# 01_DEBUG.net
KiCad netlist of a schematic drawn in Altium Designer
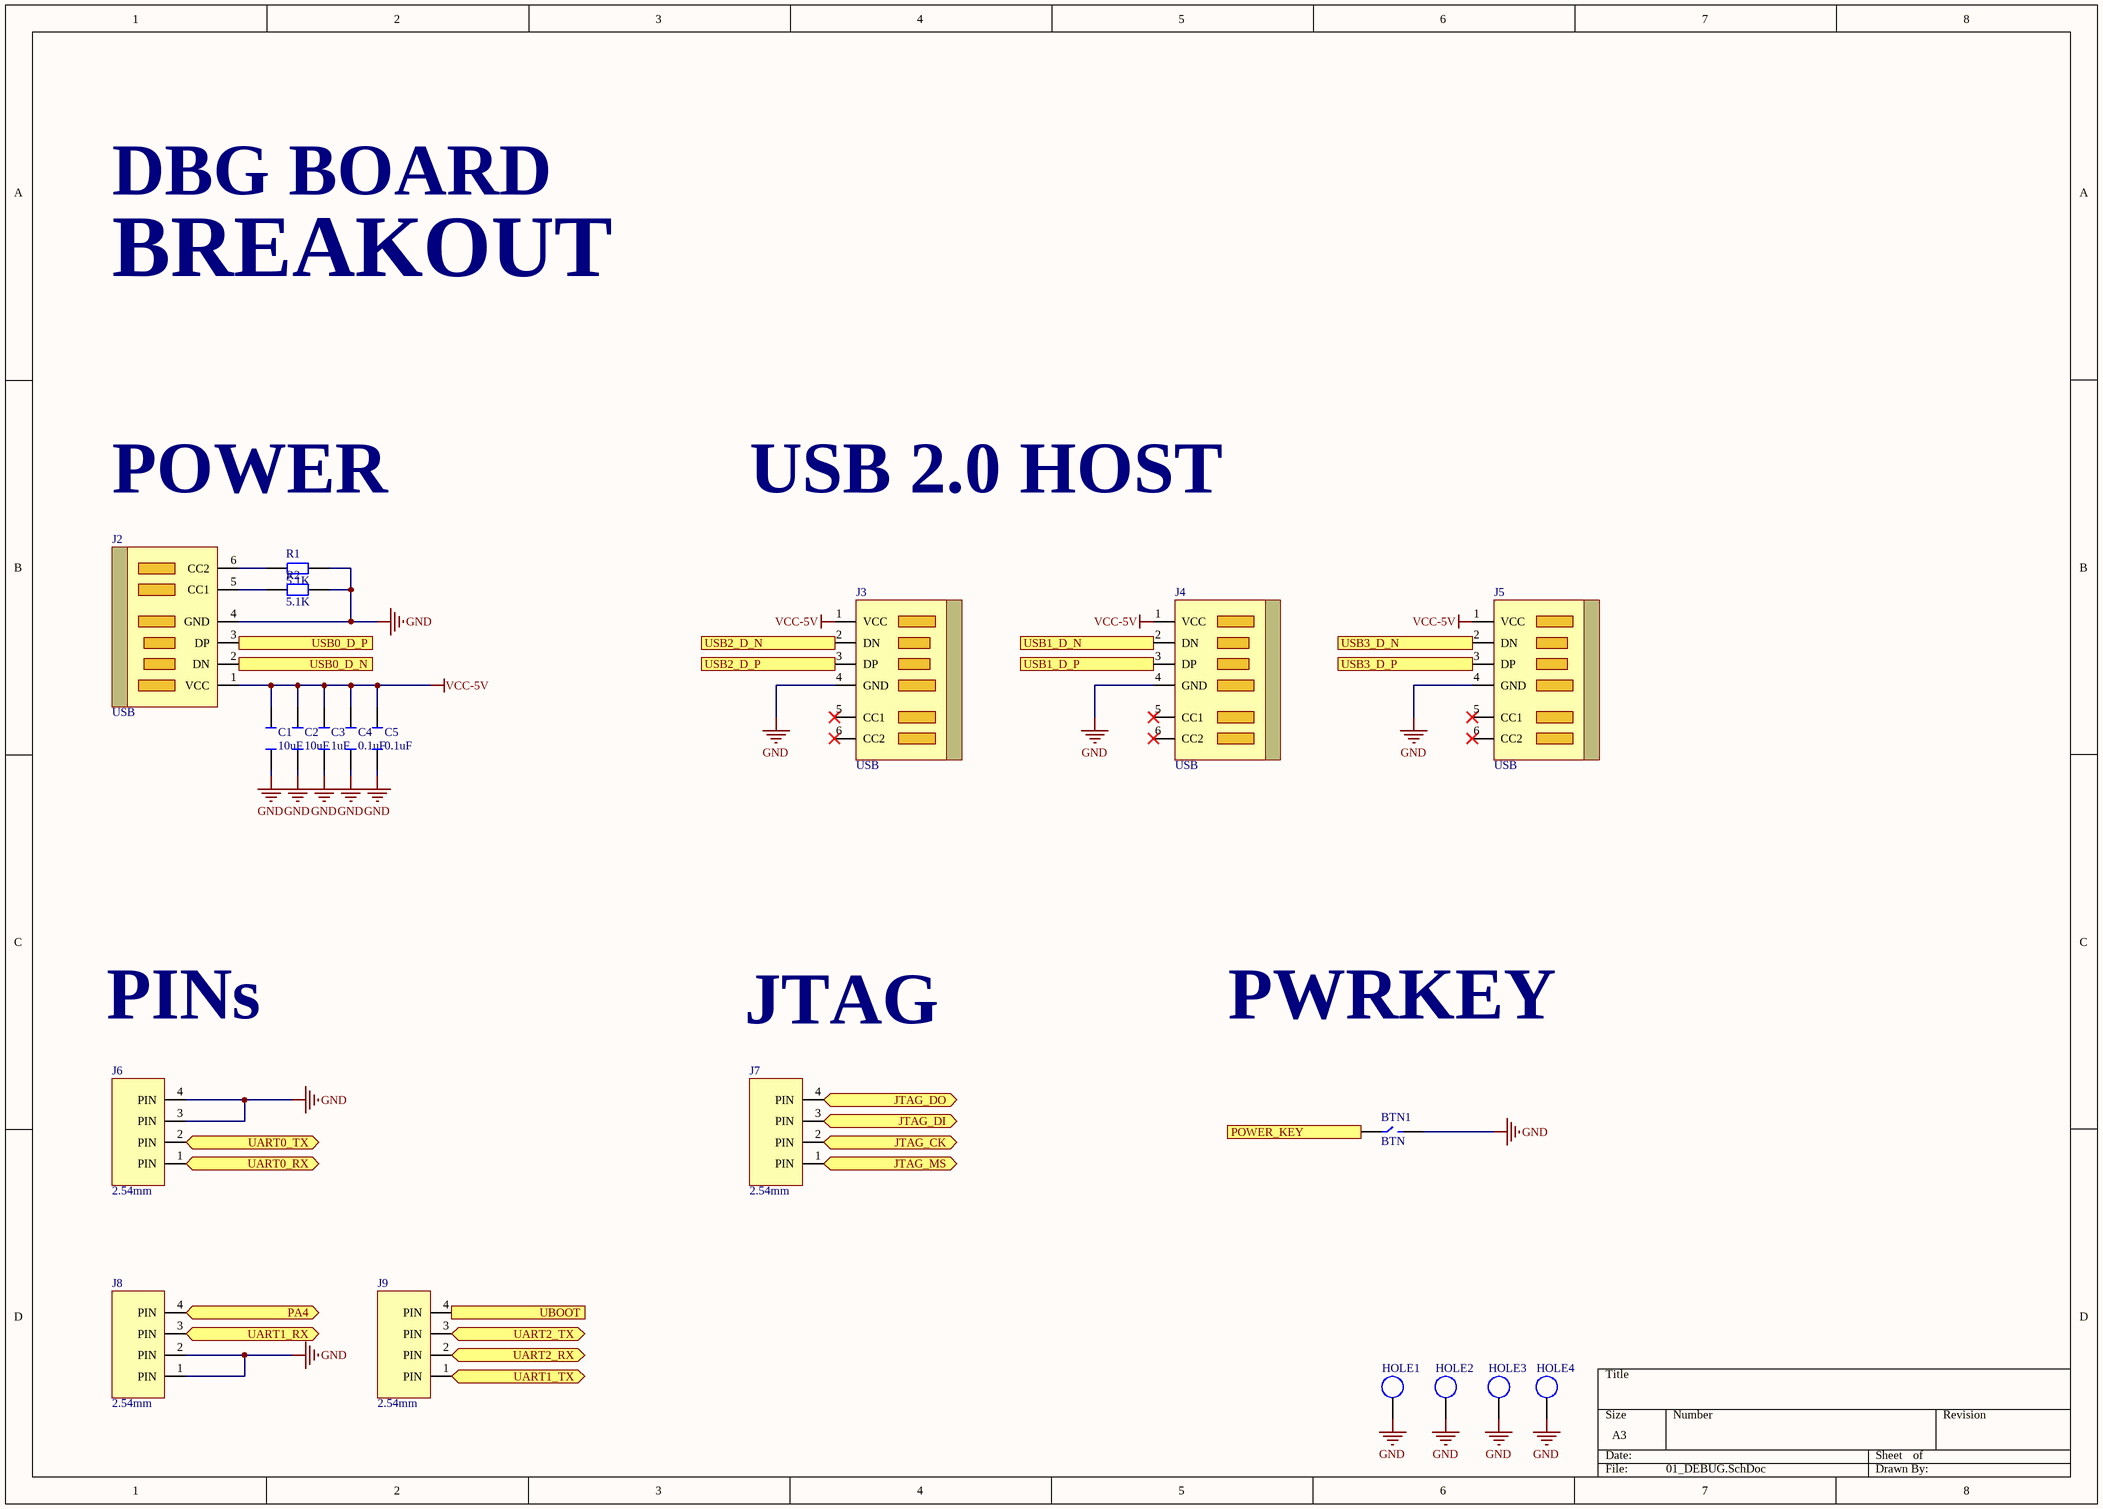
[diagram p0: 01_DEBUG.SchDoc]

(export (version "E")
  (design (tool "Eeschema 10.0.6"))
  (components
    (comp (ref "BTN1") (value "BTN") (footprint "BTN") (libsource (lib "DebugBoard") (part "BTN")))
    (comp (ref "C1") (value "10uF") (footprint "C0603") (libsource (lib "DebugBoard") (part "C_10UF")))
    (comp (ref "C2") (value "10uF") (footprint "C0603") (libsource (lib "DebugBoard") (part "C_10UF")))
    (comp (ref "C3") (value "1uF") (footprint "C0603") (libsource (lib "DebugBoard") (part "C_1UF")))
    (comp (ref "C4") (value "0.1uF") (footprint "C0603") (libsource (lib "DebugBoard") (part "C_0.1UF")))
    (comp (ref "C5") (value "0.1uF") (footprint "C0603") (libsource (lib "DebugBoard") (part "C_0.1UF")))
    (comp (ref "HOLE1")
      (value "LOADHOLE")
      (footprint "LOADHOLE")
      (libsource (lib "DebugBoard") (part "LOADHOLE"))
    )
    (comp (ref "HOLE2")
      (value "LOADHOLE")
      (footprint "LOADHOLE")
      (libsource (lib "DebugBoard") (part "LOADHOLE"))
    )
    (comp (ref "HOLE3")
      (value "LOADHOLE")
      (footprint "LOADHOLE")
      (libsource (lib "DebugBoard") (part "LOADHOLE"))
    )
    (comp (ref "HOLE4")
      (value "LOADHOLE")
      (footprint "LOADHOLE")
      (libsource (lib "DebugBoard") (part "LOADHOLE"))
    )
    (comp (ref "J2") (value "USB") (footprint "USB-4105-GF-A") (libsource (lib "DebugBoard") (part "USB")))
    (comp (ref "J3") (value "USB") (footprint "USB-A-S-S-W-TH") (libsource (lib "") (part "USB_1")))
    (comp (ref "J4") (value "USB") (footprint "USB-A-S-S-W-TH") (libsource (lib "") (part "USB_1")))
    (comp (ref "J5") (value "USB") (footprint "USB-A-S-S-W-TH") (libsource (lib "") (part "USB_1")))
    (comp (ref "J6") (value "2.54mm") (footprint "J_PIN4") (libsource (lib "DebugBoard") (part "J_PIN4")))
    (comp (ref "J7") (value "2.54mm") (footprint "J_PIN4") (libsource (lib "DebugBoard") (part "J_PIN4")))
    (comp (ref "J8") (value "2.54mm") (footprint "J_PIN4") (libsource (lib "DebugBoard") (part "J_PIN4")))
    (comp (ref "J9") (value "2.54mm") (footprint "J_PIN4") (libsource (lib "DebugBoard") (part "J_PIN4")))
    (comp (ref "R1") (value "5.1K") (footprint "R0603") (libsource (lib "DebugBoard") (part "R_5.1K")))
    (comp (ref "R2") (value "5.1K") (footprint "R0603") (libsource (lib "DebugBoard") (part "R_5.1K")))
  )
  (nets
    (net (code "1") (name "/JTAG_CK") (class "Default")
      (node (ref "J7") (pin "2") (pinfunction "PIN_2") (pintype "passive"))
    )
    (net (code "2") (name "/JTAG_DI") (class "Default")
      (node (ref "J7") (pin "3") (pinfunction "PIN_3") (pintype "passive"))
    )
    (net (code "3") (name "/JTAG_DO") (class "Default")
      (node (ref "J7") (pin "4") (pinfunction "PIN_4") (pintype "passive"))
    )
    (net (code "4") (name "/JTAG_MS") (class "Default")
      (node (ref "J7") (pin "1") (pinfunction "PIN_1") (pintype "passive"))
    )
    (net (code "5") (name "/PA4") (class "Default")
      (node (ref "J8") (pin "4") (pinfunction "PIN_4") (pintype "passive"))
    )
    (net (code "6") (name "/POWER_KEY") (class "Default") (node (ref "BTN1") (pin "1") (pintype "passive")))
    (net (code "7") (name "/UART0_RX") (class "Default")
      (node (ref "J6") (pin "1") (pinfunction "PIN_1") (pintype "passive"))
    )
    (net (code "8") (name "/UART0_TX") (class "Default")
      (node (ref "J6") (pin "2") (pinfunction "PIN_2") (pintype "passive"))
    )
    (net (code "9") (name "/UART1_RX") (class "Default")
      (node (ref "J8") (pin "3") (pinfunction "PIN_3") (pintype "passive"))
    )
    (net (code "10") (name "/UART1_TX") (class "Default")
      (node (ref "J9") (pin "1") (pinfunction "PIN_1") (pintype "passive"))
    )
    (net (code "11") (name "/UART2_RX") (class "Default")
      (node (ref "J9") (pin "2") (pinfunction "PIN_2") (pintype "passive"))
    )
    (net (code "12") (name "/UART2_TX") (class "Default")
      (node (ref "J9") (pin "3") (pinfunction "PIN_3") (pintype "passive"))
    )
    (net (code "13") (name "/UBOOT") (class "Default")
      (node (ref "J9") (pin "4") (pinfunction "PIN_4") (pintype "passive"))
    )
    (net (code "14") (name "/USB0_D_N") (class "Default")
      (node (ref "J2") (pin "2") (pinfunction "DN_2") (pintype "passive"))
    )
    (net (code "15") (name "/USB0_D_P") (class "Default")
      (node (ref "J2") (pin "3") (pinfunction "DP_3") (pintype "passive"))
    )
    (net (code "16") (name "/USB1_D_N") (class "Default")
      (node (ref "J4") (pin "2") (pinfunction "DN_2") (pintype "passive"))
    )
    (net (code "17") (name "/USB1_D_P") (class "Default")
      (node (ref "J4") (pin "3") (pinfunction "DP_3") (pintype "passive"))
    )
    (net (code "18") (name "/USB2_D_N") (class "Default")
      (node (ref "J3") (pin "2") (pinfunction "DN_2") (pintype "passive"))
    )
    (net (code "19") (name "/USB2_D_P") (class "Default")
      (node (ref "J3") (pin "3") (pinfunction "DP_3") (pintype "passive"))
    )
    (net (code "20") (name "/USB3_D_N") (class "Default")
      (node (ref "J5") (pin "2") (pinfunction "DN_2") (pintype "passive"))
    )
    (net (code "21") (name "/USB3_D_P") (class "Default")
      (node (ref "J5") (pin "3") (pinfunction "DP_3") (pintype "passive"))
    )
    (net (code "22") (name "GND") (class "Default")
      (node (ref "BTN1") (pin "2") (pintype "passive"))
      (node (ref "C1") (pin "1") (pinfunction "17_1") (pintype "passive"))
      (node (ref "C2") (pin "1") (pinfunction "17_1") (pintype "passive"))
      (node (ref "C3") (pin "1") (pinfunction "17_1") (pintype "passive"))
      (node (ref "C4") (pin "1") (pinfunction "17_1") (pintype "passive"))
      (node (ref "C5") (pin "1") (pinfunction "17_1") (pintype "passive"))
      (node (ref "HOLE1") (pin "1") (pintype "passive"))
      (node (ref "HOLE2") (pin "1") (pintype "passive"))
      (node (ref "HOLE3") (pin "1") (pintype "passive"))
      (node (ref "HOLE4") (pin "1") (pintype "passive"))
      (node (ref "J2") (pin "4") (pinfunction "GND_4") (pintype "passive"))
      (node (ref "J3") (pin "4") (pinfunction "GND_4") (pintype "passive"))
      (node (ref "J4") (pin "4") (pinfunction "GND_4") (pintype "passive"))
      (node (ref "J5") (pin "4") (pinfunction "GND_4") (pintype "passive"))
      (node (ref "J6") (pin "3") (pinfunction "PIN_3") (pintype "passive"))
      (node (ref "J6") (pin "4") (pinfunction "PIN_4") (pintype "passive"))
      (node (ref "J8") (pin "1") (pinfunction "PIN_1") (pintype "passive"))
      (node (ref "J8") (pin "2") (pinfunction "PIN_2") (pintype "passive"))
      (node (ref "R1") (pin "2") (pinfunction "18_2") (pintype "passive"))
      (node (ref "R2") (pin "2") (pinfunction "18_2") (pintype "passive"))
    )
    (net (code "23") (name "Net-(J2-CC1)") (class "Default")
      (node (ref "J2") (pin "5") (pinfunction "CC1_5") (pintype "passive"))
      (node (ref "R2") (pin "1") (pinfunction "17_1") (pintype "passive"))
    )
    (net (code "24") (name "Net-(J2-CC2)") (class "Default")
      (node (ref "J2") (pin "6") (pinfunction "CC2_6") (pintype "passive"))
      (node (ref "R1") (pin "1") (pinfunction "17_1") (pintype "passive"))
    )
    (net (code "25") (name "VCC-5V") (class "Default")
      (node (ref "C1") (pin "2") (pinfunction "18_2") (pintype "passive"))
      (node (ref "C2") (pin "2") (pinfunction "18_2") (pintype "passive"))
      (node (ref "C3") (pin "2") (pinfunction "18_2") (pintype "passive"))
      (node (ref "C4") (pin "2") (pinfunction "18_2") (pintype "passive"))
      (node (ref "C5") (pin "2") (pinfunction "18_2") (pintype "passive"))
      (node (ref "J2") (pin "1") (pinfunction "VCC_1") (pintype "passive"))
      (node (ref "J3") (pin "1") (pinfunction "VCC_1") (pintype "passive"))
      (node (ref "J4") (pin "1") (pinfunction "VCC_1") (pintype "passive"))
      (node (ref "J5") (pin "1") (pinfunction "VCC_1") (pintype "passive"))
    )
    (net (code "26") (name "unconnected-(J3-CC1-Pad5)") (class "Default")
      (node (ref "J3") (pin "5") (pinfunction "CC1_5") (pintype "passive+no_connect"))
    )
    (net (code "27") (name "unconnected-(J3-CC2-Pad6)") (class "Default")
      (node (ref "J3") (pin "6") (pinfunction "CC2_6") (pintype "passive+no_connect"))
    )
    (net (code "28") (name "unconnected-(J4-CC1-Pad5)") (class "Default")
      (node (ref "J4") (pin "5") (pinfunction "CC1_5") (pintype "passive+no_connect"))
    )
    (net (code "29") (name "unconnected-(J4-CC2-Pad6)") (class "Default")
      (node (ref "J4") (pin "6") (pinfunction "CC2_6") (pintype "passive+no_connect"))
    )
    (net (code "30") (name "unconnected-(J5-CC1-Pad5)") (class "Default")
      (node (ref "J5") (pin "5") (pinfunction "CC1_5") (pintype "passive+no_connect"))
    )
    (net (code "31") (name "unconnected-(J5-CC2-Pad6)") (class "Default")
      (node (ref "J5") (pin "6") (pinfunction "CC2_6") (pintype "passive+no_connect"))
    )
  )
)
